# pdp.net
KiCad netlist of a schematic drawn in EAGLE
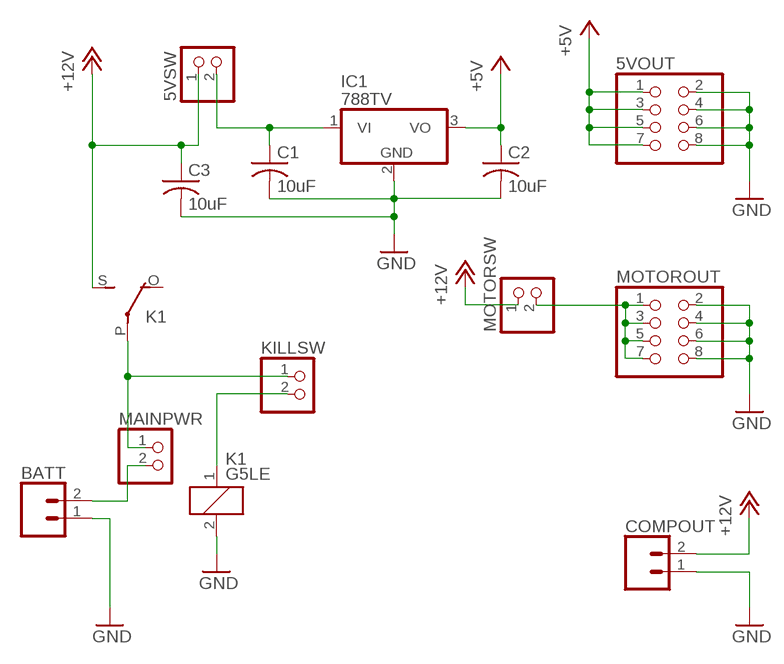
[diagram p0: schematic, sheet 1]

(export (version "E")
  (design (tool "Eeschema 10.0.6"))
  (components
    (comp (ref "5VOUT")
      (value "PINHD-2X4")
      (footprint "eagle-import:2X04")
      (libsource (lib "eagle-import") (part "PINHD-2X4"))
    )
    (comp (ref "5VSW")
      (value "PINHD-1X2")
      (footprint "eagle-import:1X02")
      (libsource (lib "eagle-import") (part "PINHD-1X2"))
    )
    (comp (ref "BATT")
      (value "CONN_025MM")
      (footprint "eagle-import:SCREWTERMINAL-5MM-2")
      (libsource (lib "eagle-import") (part "CONN_025MM"))
    )
    (comp (ref "C1")
      (value "10uF")
      (footprint "eagle-import:C0805")
      (libsource (lib "eagle-import") (part "C-USC0805"))
    )
    (comp (ref "C2")
      (value "10uF")
      (footprint "eagle-import:C0805")
      (libsource (lib "eagle-import") (part "C-USC0805"))
    )
    (comp (ref "C3")
      (value "10uF")
      (footprint "eagle-import:C0805")
      (libsource (lib "eagle-import") (part "C-USC0805"))
    )
    (comp (ref "COMPOUT")
      (value "CONN_025MM")
      (footprint "eagle-import:SCREWTERMINAL-5MM-2")
      (libsource (lib "eagle-import") (part "CONN_025MM"))
    )
    (comp (ref "IC1")
      (value "788TV")
      (footprint "eagle-import:TO220V")
      (libsource (lib "eagle-import") (part "78TV8"))
    )
    (comp (ref "K1")
      (value "G5LE")
      (footprint "eagle-import:G5LE")
      (libsource (lib "eagle-import") (part "G5LE"))
    )
    (comp (ref "KILLSW")
      (value "PINHD-1X2")
      (footprint "eagle-import:1X02")
      (libsource (lib "eagle-import") (part "PINHD-1X2"))
    )
    (comp (ref "MAINPWR")
      (value "PINHD-1X2")
      (footprint "eagle-import:1X02")
      (libsource (lib "eagle-import") (part "PINHD-1X2"))
    )
    (comp (ref "MOTOROUT")
      (value "PINHD-2X4")
      (footprint "eagle-import:2X04")
      (libsource (lib "eagle-import") (part "PINHD-2X4"))
    )
    (comp (ref "MOTORSW")
      (value "PINHD-1X2")
      (footprint "eagle-import:1X02")
      (libsource (lib "eagle-import") (part "PINHD-1X2"))
    )
  )
  (nets
    (net (code "1") (name "+5V") (class "Default")
      (node (ref "5VOUT") (pin "1") (pinfunction "1_1") (pintype "passive"))
      (node (ref "5VOUT") (pin "3") (pinfunction "3_3") (pintype "passive"))
      (node (ref "5VOUT") (pin "5") (pinfunction "5_5") (pintype "passive"))
      (node (ref "5VOUT") (pin "7") (pinfunction "7_7") (pintype "passive"))
      (node (ref "C2") (pin "1") (pinfunction "1_1") (pintype "passive"))
      (node (ref "IC1") (pin "3") (pinfunction "VO_3") (pintype "passive"))
    )
    (net (code "2") (name "+12V") (class "Default")
      (node (ref "5VSW") (pin "1") (pinfunction "1_1") (pintype "passive"))
      (node (ref "C3") (pin "1") (pinfunction "1_1") (pintype "passive"))
      (node (ref "COMPOUT") (pin "2") (pinfunction "2_2") (pintype "passive"))
      (node (ref "K1") (pin "S") (pinfunction "S_S") (pintype "passive"))
      (node (ref "MOTORSW") (pin "1") (pinfunction "1_1") (pintype "passive"))
    )
    (net (code "3") (name "GND") (class "Default")
      (node (ref "5VOUT") (pin "2") (pinfunction "2_2") (pintype "passive"))
      (node (ref "5VOUT") (pin "4") (pinfunction "4_4") (pintype "passive"))
      (node (ref "5VOUT") (pin "6") (pinfunction "6_6") (pintype "passive"))
      (node (ref "5VOUT") (pin "8") (pinfunction "8_8") (pintype "passive"))
      (node (ref "BATT") (pin "1") (pinfunction "1_1") (pintype "passive"))
      (node (ref "C1") (pin "2") (pinfunction "2_2") (pintype "passive"))
      (node (ref "C2") (pin "2") (pinfunction "2_2") (pintype "passive"))
      (node (ref "C3") (pin "2") (pinfunction "2_2") (pintype "passive"))
      (node (ref "COMPOUT") (pin "1") (pinfunction "1_1") (pintype "passive"))
      (node (ref "IC1") (pin "2") (pinfunction "GND_2") (pintype "passive"))
      (node (ref "K1") (pin "2") (pinfunction "2_2") (pintype "passive"))
      (node (ref "MOTOROUT") (pin "2") (pinfunction "2_2") (pintype "passive"))
      (node (ref "MOTOROUT") (pin "4") (pinfunction "4_4") (pintype "passive"))
      (node (ref "MOTOROUT") (pin "6") (pinfunction "6_6") (pintype "passive"))
      (node (ref "MOTOROUT") (pin "8") (pinfunction "8_8") (pintype "passive"))
    )
    (net (code "4") (name "Net-(BATT-Pad2)") (class "Default")
      (node (ref "BATT") (pin "2") (pinfunction "2_2") (pintype "passive"))
      (node (ref "MAINPWR") (pin "2") (pinfunction "2_2") (pintype "passive"))
    )
    (net (code "5") (name "Net-(IC1-VI)") (class "Default")
      (node (ref "5VSW") (pin "2") (pinfunction "2_2") (pintype "passive"))
      (node (ref "C1") (pin "1") (pinfunction "1_1") (pintype "passive"))
      (node (ref "IC1") (pin "1") (pinfunction "VI_1") (pintype "input"))
    )
    (net (code "6") (name "Net-(K1-Pad1)") (class "Default")
      (node (ref "K1") (pin "1") (pinfunction "1_1") (pintype "passive"))
      (node (ref "KILLSW") (pin "2") (pinfunction "2_2") (pintype "passive"))
    )
    (net (code "7") (name "Net-(K1-PadP)") (class "Default")
      (node (ref "K1") (pin "P") (pinfunction "P_P") (pintype "passive"))
      (node (ref "KILLSW") (pin "1") (pinfunction "1_1") (pintype "passive"))
      (node (ref "MAINPWR") (pin "1") (pinfunction "1_1") (pintype "passive"))
    )
    (net (code "8") (name "Net-(MOTOROUT-Pad1)") (class "Default")
      (node (ref "MOTOROUT") (pin "1") (pinfunction "1_1") (pintype "passive"))
      (node (ref "MOTOROUT") (pin "3") (pinfunction "3_3") (pintype "passive"))
      (node (ref "MOTOROUT") (pin "5") (pinfunction "5_5") (pintype "passive"))
      (node (ref "MOTOROUT") (pin "7") (pinfunction "7_7") (pintype "passive"))
      (node (ref "MOTORSW") (pin "2") (pinfunction "2_2") (pintype "passive"))
    )
    (net (code "9") (name "unconnected-(K1-PadO)") (class "Default")
      (node (ref "K1") (pin "O") (pinfunction "O_O") (pintype "passive"))
    )
  )
)
